# 7_-H3_POWER.net
KiCad netlist of a schematic drawn in Altium Designer
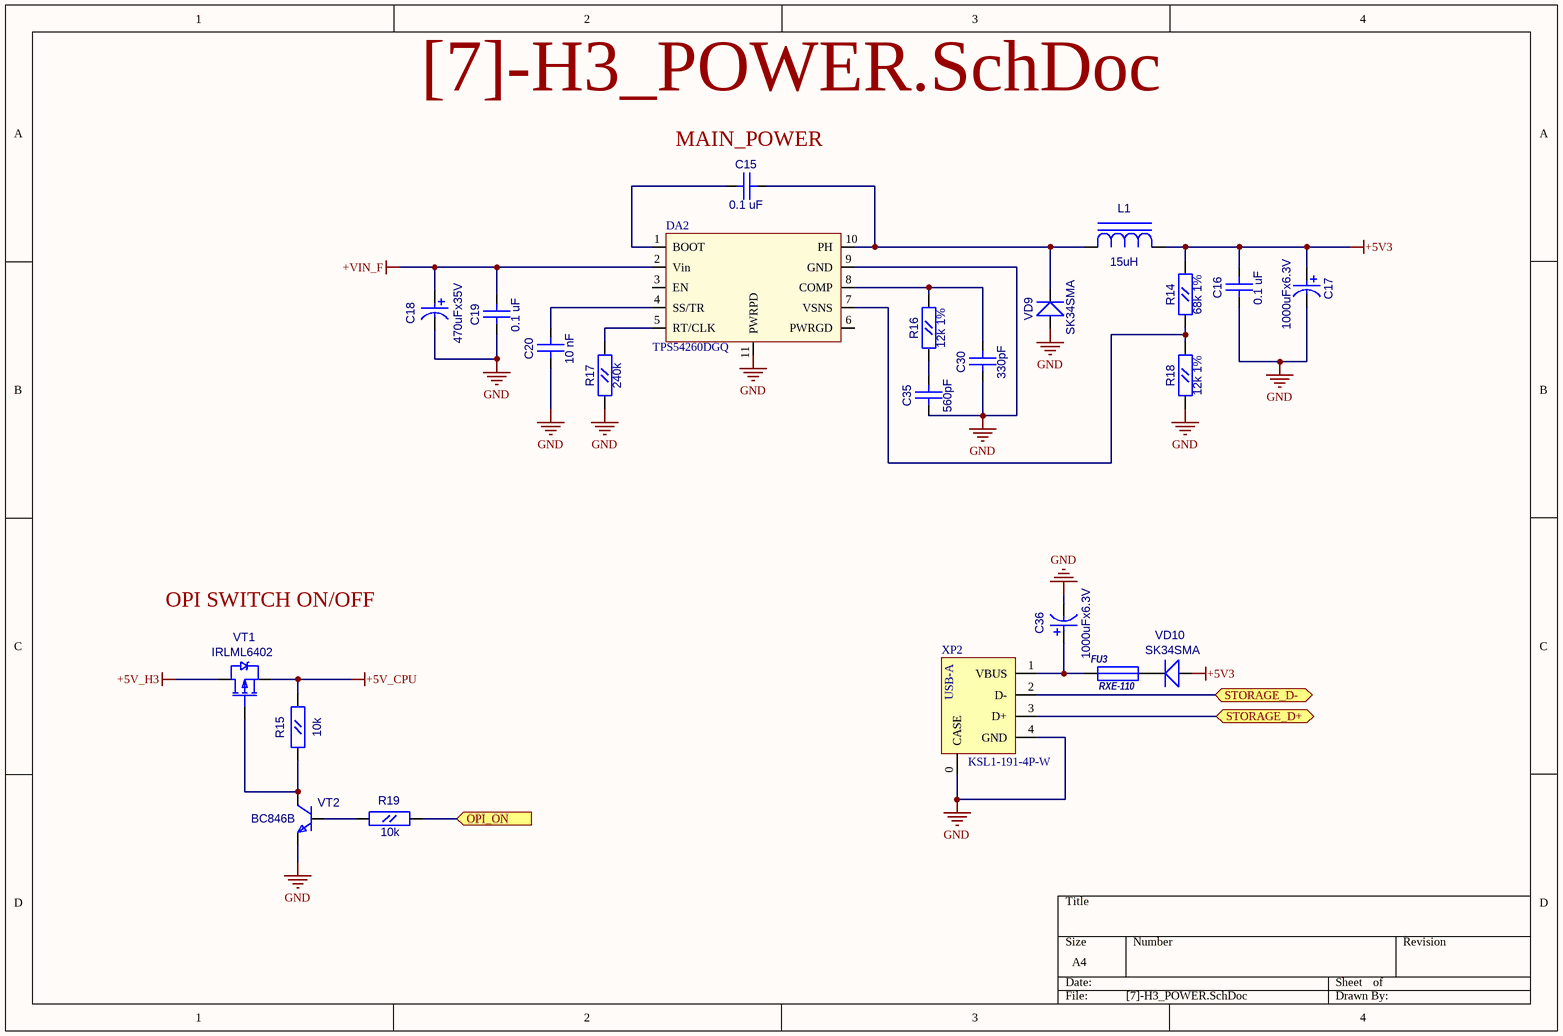
[diagram p0: [7]-H3_POWER.SchDoc]

(export (version "E")
  (design (tool "Eeschema 10.0.6"))
  (components
    (comp (ref "C15")
      (value "0.1 uF")
      (footprint "CC0603")
      (description "CC0603")
      (libsource (lib "gprs_modem_2") (part "CC0603"))
    )
    (comp (ref "C16")
      (value "0.1 uF")
      (footprint "CC0603")
      (description "CC0603")
      (libsource (lib "gprs_modem_2") (part "CC0603"))
    )
    (comp (ref "C17")
      (value "1000uFx6.3V")
      (footprint "CC8X3.5")
      (description "CAP0.35")
      (libsource (lib "gprs_modem_2") (part "CAP0.35"))
    )
    (comp (ref "C18")
      (value "470uFx35V")
      (footprint "CC16X10_CAP0.5(1)(Primary)")
      (description "CAP0.5(1)")
      (libsource (lib "gprs_modem_2") (part "CAP0.5(1)"))
    )
    (comp (ref "C19")
      (value "0.1 uF")
      (footprint "CC0603")
      (description "CC0603")
      (libsource (lib "gprs_modem_2") (part "CC0603"))
    )
    (comp (ref "C20")
      (value "10 nF")
      (footprint "CC0603")
      (description "CC0603")
      (libsource (lib "gprs_modem_2") (part "CC0603"))
    )
    (comp (ref "C30")
      (value "330pF")
      (footprint "CC0603")
      (description "CC0603")
      (libsource (lib "gprs_modem_2") (part "CC0603"))
    )
    (comp (ref "C35")
      (value "560pF")
      (footprint "CC0603")
      (description "CC0603")
      (libsource (lib "gprs_modem_2") (part "CC0603"))
    )
    (comp (ref "C36")
      (value "1000uFx6.3V")
      (footprint "CC8X3.5")
      (description "CAP0.35")
      (libsource (lib "gprs_modem_2") (part "CAP0.35"))
    )
    (comp (ref "DA2")
      (value "TPS54260DGQ")
      (footprint "S-PDSO-G10")
      (libsource (lib "gprs_modem_2") (part "TPS54260DGQ"))
    )
    (comp (ref "FU3")
      (value "RXE-110")
      (footprint "RXE-110")
      (libsource (lib "fizik_lib (1)") (part "RXE-110"))
    )
    (comp (ref "L1")
      (value "15uH")
      (footprint "SDR0805")
      (description "SDR0805")
      (libsource (lib "gprs_modem_2") (part "SDR0805"))
    )
    (comp (ref "R14")
      (value "68k 1%")
      (footprint "RC0603")
      (description "RC0603")
      (libsource (lib "gprs_modem_2") (part "RC0603"))
    )
    (comp (ref "R15")
      (value "10k")
      (footprint "RC0603")
      (description "RC0603")
      (libsource (lib "gprs_modem_2") (part "RC0603"))
    )
    (comp (ref "R16")
      (value "12k 1%")
      (footprint "RC0603")
      (description "RC0603")
      (libsource (lib "gprs_modem_2") (part "RC0603"))
    )
    (comp (ref "R17")
      (value "240k")
      (footprint "RC0603")
      (description "RC0603")
      (libsource (lib "gprs_modem_2") (part "RC0603"))
    )
    (comp (ref "R18")
      (value "12k 1%")
      (footprint "RC0603")
      (description "RC0603")
      (libsource (lib "gprs_modem_2") (part "RC0603"))
    )
    (comp (ref "R19")
      (value "10k")
      (footprint "RC0603")
      (description "RC0603")
      (libsource (lib "fizik_lib") (part "RC0603"))
    )
    (comp (ref "VD9")
      (value "SK34SMA")
      (footprint "SMA")
      (description "Schottky Rectifier")
      (libsource (lib "gprs_modem") (part "SK34SMA"))
    )
    (comp (ref "VD10")
      (value "SK34SMA")
      (footprint "SMA")
      (description "Schottky Rectifier")
      (libsource (lib "gprs_modem") (part "SK34SMA"))
    )
    (comp (ref "VT1")
      (value "IRLML6402")
      (footprint "SOT-23(123)")
      (description "HEXFET Power MOSFET")
      (libsource (lib "gprs_modem_2") (part "IRLML6402"))
    )
    (comp (ref "VT2")
      (value "BC846B")
      (footprint "SOT-23(123)")
      (description "BC846BLT1")
      (libsource (lib "gprs_modem_2") (part "BC846BLT1"))
    )
    (comp (ref "XP2")
      (value "KSL1-191-4P-W")
      (footprint "USB_A_REAR")
      (description "USB A rear side connector")
      (libsource (lib "fizik_lib") (part "USB_A_REAR"))
    )
  )
  (nets
    (net (code "1") (name "+5V3") (class "Default")
      (node (ref "C16") (pin "1") (pinfunction "A_1") (pintype "passive"))
      (node (ref "C17") (pin "1") (pintype "passive"))
      (node (ref "L1") (pin "2") (pinfunction "A_2") (pintype "passive"))
      (node (ref "R14") (pin "2") (pinfunction "B_2") (pintype "passive"))
      (node (ref "VD10") (pin "1") (pinfunction "A_1") (pintype "passive"))
    )
    (net (code "2") (name "+5V_CPU") (class "Default")
      (node (ref "R15") (pin "2") (pinfunction "B_2") (pintype "passive"))
      (node (ref "VT1") (pin "2") (pinfunction "S_2") (pintype "passive"))
    )
    (net (code "3") (name "+5V_H3") (class "Default")
      (node (ref "VT1") (pin "3") (pinfunction "D_3") (pintype "passive"))
    )
    (net (code "4") (name "+VIN_F") (class "Default")
      (node (ref "C18") (pin "2") (pintype "passive"))
      (node (ref "C19") (pin "1") (pinfunction "A_1") (pintype "passive"))
      (node (ref "DA2") (pin "2") (pinfunction "Vin_2") (pintype "passive"))
    )
    (net (code "5") (name "/OPI_ON") (class "Default")
      (node (ref "R19") (pin "2") (pinfunction "B_2") (pintype "passive"))
    )
    (net (code "6") (name "/STORAGE_D+") (class "Default")
      (node (ref "XP2") (pin "3") (pinfunction "D+_3") (pintype "passive"))
    )
    (net (code "7") (name "/STORAGE_D-") (class "Default")
      (node (ref "XP2") (pin "2") (pinfunction "D-_2") (pintype "passive"))
    )
    (net (code "8") (name "GND") (class "Default")
      (node (ref "C16") (pin "2") (pinfunction "B_2") (pintype "passive"))
      (node (ref "C17") (pin "2") (pintype "passive"))
      (node (ref "C18") (pin "1") (pintype "passive"))
      (node (ref "C19") (pin "2") (pinfunction "B_2") (pintype "passive"))
      (node (ref "C20") (pin "2") (pinfunction "B_2") (pintype "passive"))
      (node (ref "C30") (pin "2") (pinfunction "B_2") (pintype "passive"))
      (node (ref "C35") (pin "2") (pinfunction "B_2") (pintype "passive"))
      (node (ref "C36") (pin "2") (pintype "passive"))
      (node (ref "DA2") (pin "11") (pinfunction "PWRPD_11") (pintype "passive"))
      (node (ref "DA2") (pin "9") (pinfunction "GND_9") (pintype "passive"))
      (node (ref "R17") (pin "1") (pinfunction "A_1") (pintype "passive"))
      (node (ref "R18") (pin "1") (pinfunction "A_1") (pintype "passive"))
      (node (ref "VD9") (pin "1") (pinfunction "A_1") (pintype "passive"))
      (node (ref "VT2") (pin "2") (pinfunction "E_2") (pintype "passive"))
      (node (ref "XP2") (pin "0") (pinfunction "CASE_0") (pintype "passive"))
      (node (ref "XP2") (pin "4") (pinfunction "GND_4") (pintype "passive"))
    )
    (net (code "9") (name "Net-(C15-A)") (class "Default")
      (node (ref "C15") (pin "1") (pinfunction "A_1") (pintype "passive"))
      (node (ref "DA2") (pin "10") (pinfunction "PH_10") (pintype "passive"))
      (node (ref "L1") (pin "1") (pinfunction "C_1") (pintype "passive"))
      (node (ref "VD9") (pin "2") (pinfunction "K_2") (pintype "passive"))
    )
    (net (code "10") (name "Net-(C15-B)") (class "Default")
      (node (ref "C15") (pin "2") (pinfunction "B_2") (pintype "passive"))
      (node (ref "DA2") (pin "1") (pinfunction "BOOT_1") (pintype "passive"))
    )
    (net (code "11") (name "Net-(C20-A)") (class "Default")
      (node (ref "C20") (pin "1") (pinfunction "A_1") (pintype "passive"))
      (node (ref "DA2") (pin "4") (pinfunction "SS/TR_4") (pintype "passive"))
    )
    (net (code "12") (name "Net-(C30-A)") (class "Default")
      (node (ref "C30") (pin "1") (pinfunction "A_1") (pintype "passive"))
      (node (ref "DA2") (pin "8") (pinfunction "COMP_8") (pintype "passive"))
      (node (ref "R16") (pin "2") (pinfunction "B_2") (pintype "passive"))
    )
    (net (code "13") (name "Net-(C35-A)") (class "Default")
      (node (ref "C35") (pin "1") (pinfunction "A_1") (pintype "passive"))
      (node (ref "R16") (pin "1") (pinfunction "A_1") (pintype "passive"))
    )
    (net (code "14") (name "Net-(DA2-RT{slash}CLK)") (class "Default")
      (node (ref "DA2") (pin "5") (pinfunction "RT/CLK_5") (pintype "passive"))
      (node (ref "R17") (pin "2") (pinfunction "B_2") (pintype "passive"))
    )
    (net (code "15") (name "Net-(DA2-VSNS)") (class "Default")
      (node (ref "DA2") (pin "7") (pinfunction "VSNS_7") (pintype "passive"))
      (node (ref "R14") (pin "1") (pinfunction "A_1") (pintype "passive"))
      (node (ref "R18") (pin "2") (pinfunction "B_2") (pintype "passive"))
    )
    (net (code "16") (name "Net-(R15-A)") (class "Default")
      (node (ref "R15") (pin "1") (pinfunction "A_1") (pintype "passive"))
      (node (ref "VT1") (pin "1") (pinfunction "G_1") (pintype "passive"))
      (node (ref "VT2") (pin "3") (pinfunction "C_3") (pintype "passive"))
    )
    (net (code "17") (name "Net-(R19-A)") (class "Default")
      (node (ref "R19") (pin "1") (pinfunction "A_1") (pintype "passive"))
      (node (ref "VT2") (pin "1") (pinfunction "B_1") (pintype "passive"))
    )
    (net (code "18") (name "Net-(VD10-K)") (class "Default")
      (node (ref "FU3") (pin "2") (pintype "passive"))
      (node (ref "VD10") (pin "2") (pinfunction "K_2") (pintype "passive"))
    )
    (net (code "19") (name "Net-(XP2-VBUS)") (class "Default")
      (node (ref "C36") (pin "1") (pintype "passive"))
      (node (ref "FU3") (pin "1") (pintype "passive"))
      (node (ref "XP2") (pin "1") (pinfunction "VBUS_1") (pintype "passive"))
    )
    (net (code "20") (name "unconnected-(DA2-EN-Pad3)") (class "Default")
      (node (ref "DA2") (pin "3") (pinfunction "EN_3") (pintype "passive"))
    )
    (net (code "21") (name "unconnected-(DA2-PWRGD-Pad6)") (class "Default")
      (node (ref "DA2") (pin "6") (pinfunction "PWRGD_6") (pintype "passive"))
    )
  )
)
